# dabpi_v11.net
KiCad netlist of a schematic drawn in EAGLE
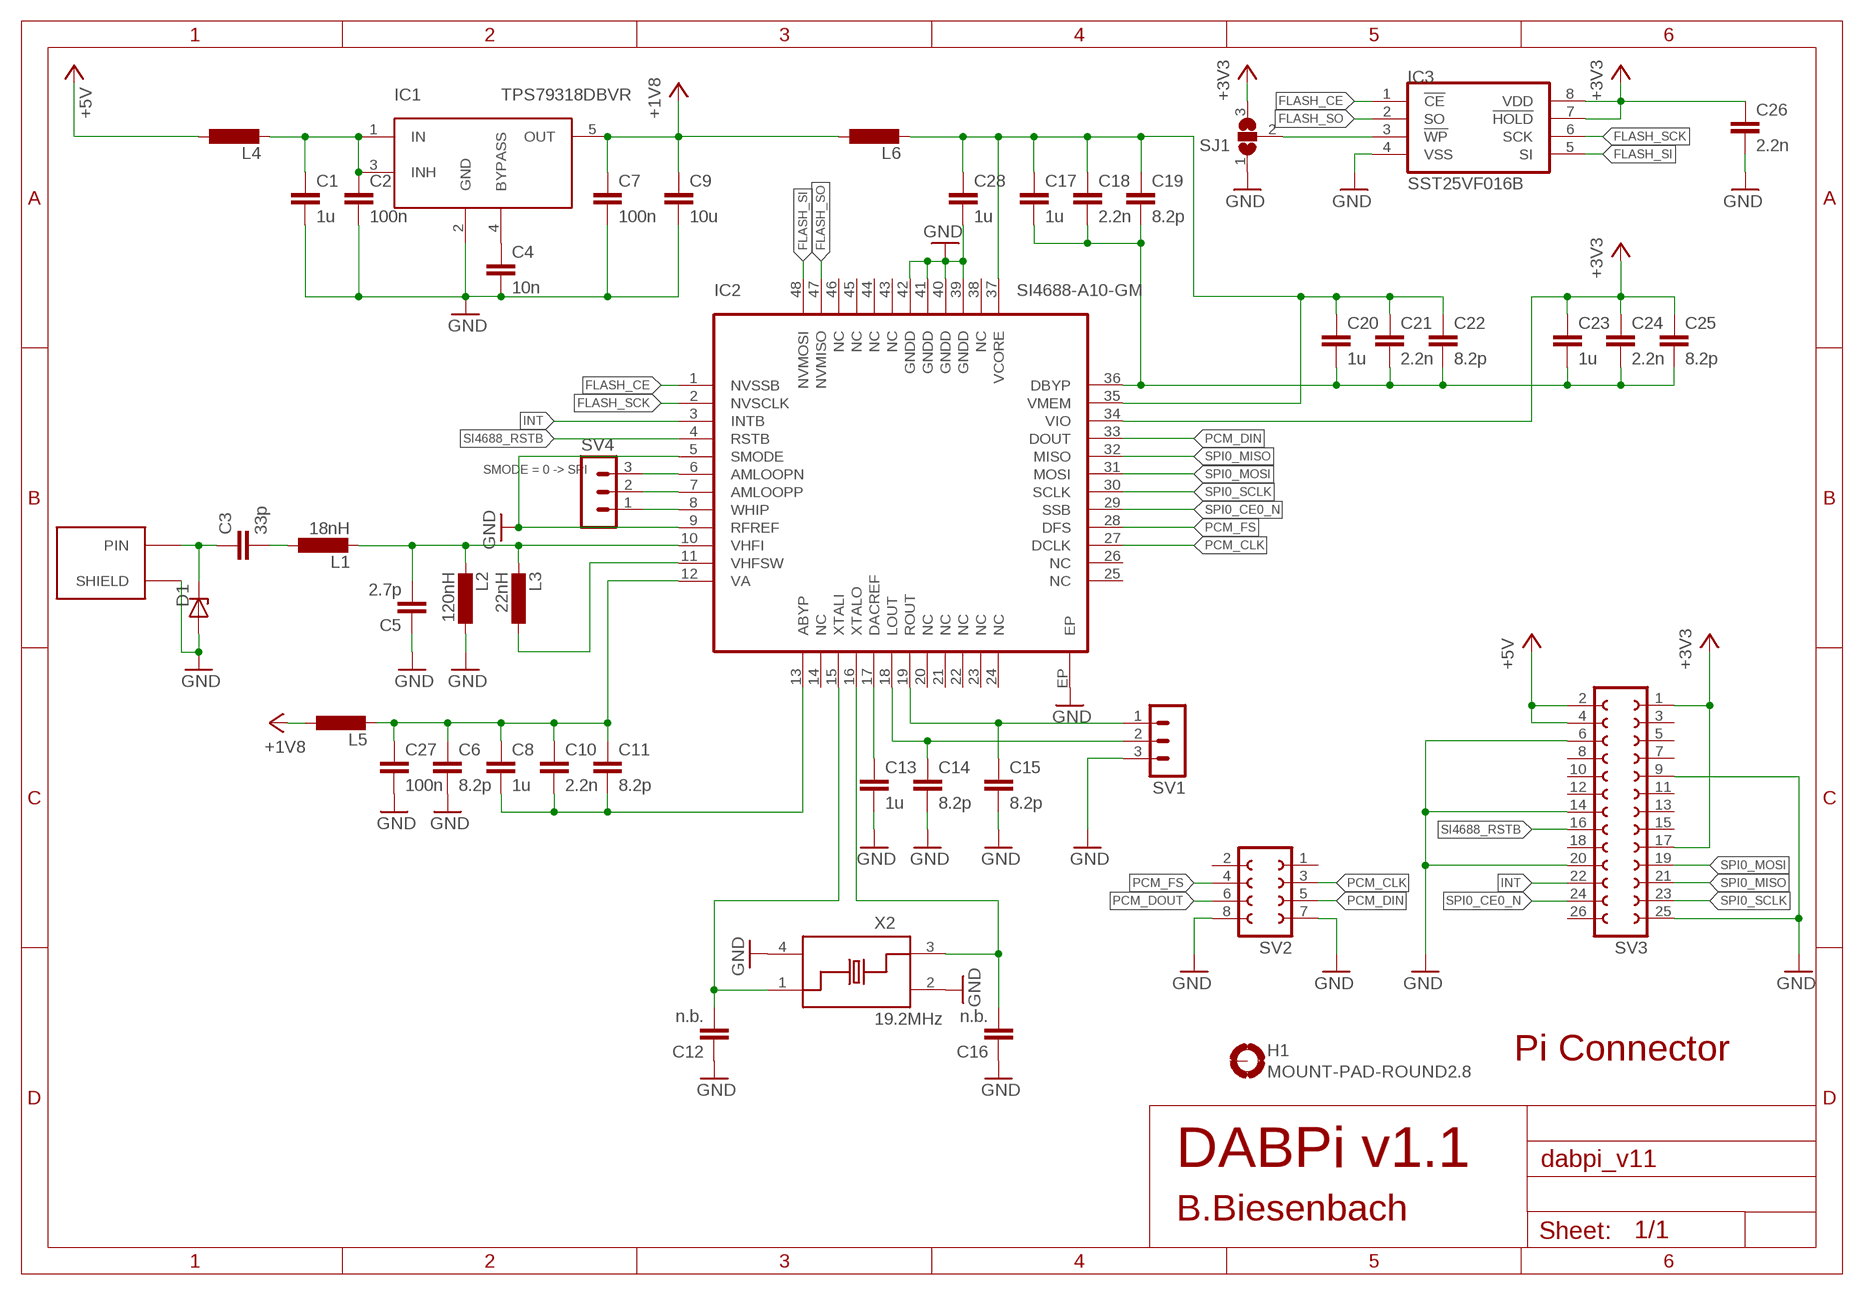
[diagram p0: schematic, sheet 1]

(export (version "E")
  (design (tool "Eeschema 10.0.6"))
  (components
    (comp (ref "C1")
      (value "1u")
      (footprint "eagle-import:SMD0603")
      (libsource (lib "eagle-import") (part "C0603"))
    )
    (comp (ref "C2")
      (value "100n")
      (footprint "eagle-import:SMD0603")
      (libsource (lib "eagle-import") (part "C0603"))
    )
    (comp (ref "C3")
      (value "33p")
      (footprint "eagle-import:SMD0402")
      (libsource (lib "eagle-import") (part "C0402"))
    )
    (comp (ref "C4")
      (value "10n")
      (footprint "eagle-import:SMD0603")
      (libsource (lib "eagle-import") (part "C0603"))
    )
    (comp (ref "C5")
      (value "2.7p")
      (footprint "eagle-import:SMD0402")
      (libsource (lib "eagle-import") (part "C0402"))
    )
    (comp (ref "C6")
      (value "8.2p")
      (footprint "eagle-import:SMD0603")
      (libsource (lib "eagle-import") (part "C0603"))
    )
    (comp (ref "C7")
      (value "100n")
      (footprint "eagle-import:SMD0603")
      (libsource (lib "eagle-import") (part "C0603"))
    )
    (comp (ref "C8")
      (value "1u")
      (footprint "eagle-import:SMD0603")
      (libsource (lib "eagle-import") (part "C0603"))
    )
    (comp (ref "C9")
      (value "10u")
      (footprint "eagle-import:SMD0603")
      (libsource (lib "eagle-import") (part "C0603"))
    )
    (comp (ref "C10")
      (value "2.2n")
      (footprint "eagle-import:SMD0603")
      (libsource (lib "eagle-import") (part "C0603"))
    )
    (comp (ref "C11")
      (value "8.2p")
      (footprint "eagle-import:SMD0603")
      (libsource (lib "eagle-import") (part "C0603"))
    )
    (comp (ref "C12")
      (value "n.b.")
      (footprint "eagle-import:SMD0402")
      (libsource (lib "eagle-import") (part "C0402"))
    )
    (comp (ref "C13")
      (value "1u")
      (footprint "eagle-import:SMD0603")
      (libsource (lib "eagle-import") (part "C0603"))
    )
    (comp (ref "C14")
      (value "8.2p")
      (footprint "eagle-import:SMD0603")
      (libsource (lib "eagle-import") (part "C0603"))
    )
    (comp (ref "C15")
      (value "8.2p")
      (footprint "eagle-import:SMD0603")
      (libsource (lib "eagle-import") (part "C0603"))
    )
    (comp (ref "C16")
      (value "n.b.")
      (footprint "eagle-import:SMD0402")
      (libsource (lib "eagle-import") (part "C0402"))
    )
    (comp (ref "C17")
      (value "1u")
      (footprint "eagle-import:SMD0603")
      (libsource (lib "eagle-import") (part "C0603"))
    )
    (comp (ref "C18")
      (value "2.2n")
      (footprint "eagle-import:SMD0603")
      (libsource (lib "eagle-import") (part "C0603"))
    )
    (comp (ref "C19")
      (value "8.2p")
      (footprint "eagle-import:SMD0603")
      (libsource (lib "eagle-import") (part "C0603"))
    )
    (comp (ref "C20")
      (value "1u")
      (footprint "eagle-import:SMD0603")
      (libsource (lib "eagle-import") (part "C0603"))
    )
    (comp (ref "C21")
      (value "2.2n")
      (footprint "eagle-import:SMD0603")
      (libsource (lib "eagle-import") (part "C0603"))
    )
    (comp (ref "C22")
      (value "8.2p")
      (footprint "eagle-import:SMD0603")
      (libsource (lib "eagle-import") (part "C0603"))
    )
    (comp (ref "C23")
      (value "1u")
      (footprint "eagle-import:SMD0603")
      (libsource (lib "eagle-import") (part "C0603"))
    )
    (comp (ref "C24")
      (value "2.2n")
      (footprint "eagle-import:SMD0603")
      (libsource (lib "eagle-import") (part "C0603"))
    )
    (comp (ref "C25")
      (value "8.2p")
      (footprint "eagle-import:SMD0603")
      (libsource (lib "eagle-import") (part "C0603"))
    )
    (comp (ref "C26")
      (value "2.2n")
      (footprint "eagle-import:SMD0603")
      (libsource (lib "eagle-import") (part "C0603"))
    )
    (comp (ref "C27")
      (value "100n")
      (footprint "eagle-import:SMD0603")
      (libsource (lib "eagle-import") (part "C0603"))
    )
    (comp (ref "C28")
      (value "1u")
      (footprint "eagle-import:SMD0603")
      (libsource (lib "eagle-import") (part "C0603"))
    )
    (comp (ref "D1")
      (value "ESD9L5.0")
      (footprint "eagle-import:SOD923")
      (libsource (lib "eagle-import") (part "ESD9L5.0"))
    )
    (comp (ref "H1")
      (value "MOUNT-PAD-ROUND2.8")
      (footprint "eagle-import:2,8-PAD")
      (libsource (lib "eagle-import") (part "MOUNT-PAD-ROUND2.8"))
    )
    (comp (ref "IC1")
      (value "TPS79318DBVR")
      (footprint "eagle-import:SOT23-5")
      (libsource (lib "eagle-import") (part "TPS79318DBVR"))
    )
    (comp (ref "IC2")
      (value "SI4688-A10-GM")
      (footprint "eagle-import:QFN48")
      (libsource (lib "eagle-import") (part "SI4688-A10-GM"))
    )
    (comp (ref "IC3")
      (value "SST25VF016B")
      (footprint "eagle-import:SO08")
      (libsource (lib "eagle-import") (part "SST25VF016B"))
    )
    (comp (ref "L1")
      (value "18nH")
      (footprint "eagle-import:SMD0402")
      (libsource (lib "eagle-import") (part "L0402"))
    )
    (comp (ref "L2")
      (value "120nH")
      (footprint "eagle-import:SMD0402")
      (libsource (lib "eagle-import") (part "L0402"))
    )
    (comp (ref "L3")
      (value "22nH")
      (footprint "eagle-import:SMD0402")
      (libsource (lib "eagle-import") (part "L0402"))
    )
    (comp (ref "L4")
      (value "L0603")
      (footprint "eagle-import:SMD0603")
      (libsource (lib "eagle-import") (part "L0603"))
    )
    (comp (ref "L5")
      (value "L0603")
      (footprint "eagle-import:SMD0603")
      (libsource (lib "eagle-import") (part "L0603"))
    )
    (comp (ref "L6")
      (value "L0603")
      (footprint "eagle-import:SMD0603")
      (libsource (lib "eagle-import") (part "L0603"))
    )
    (comp (ref "SJ1")
      (value "SJ2W")
      (footprint "eagle-import:SJ_2")
      (libsource (lib "eagle-import") (part "SJ2W"))
    )
    (comp (ref "SV1")
      (value "MA03-1")
      (footprint "eagle-import:MA03-1")
      (libsource (lib "eagle-import") (part "MA03-1"))
    )
    (comp (ref "SV2")
      (value "FE04-2")
      (footprint "eagle-import:FE04-2")
      (libsource (lib "eagle-import") (part "FE04-2"))
    )
    (comp (ref "SV3")
      (value "FE13-2")
      (footprint "eagle-import:FE13-2")
      (libsource (lib "eagle-import") (part "FE13-2"))
    )
    (comp (ref "SV4")
      (value "MA03-1")
      (footprint "eagle-import:MA03-1")
      (libsource (lib "eagle-import") (part "MA03-1"))
    )
    (comp (ref "X1")
      (value "SMA_LP_1.57MM")
      (footprint "eagle-import:SMA_LP_1.57MM")
      (libsource (lib "eagle-import") (part "SMA_LP_1.57MM"))
    )
    (comp (ref "X2")
      (value "19.2MHz")
      (footprint "eagle-import:XTAL_3.2X2.5")
      (libsource (lib "eagle-import") (part "XTAL_3.2X2.5"))
    )
  )
  (nets
    (net (code "1") (name "+1V8") (class "Default")
      (node (ref "C7") (pin "1") (pinfunction "1_1") (pintype "passive"))
      (node (ref "C9") (pin "1") (pinfunction "1_1") (pintype "passive"))
      (node (ref "IC1") (pin "5") (pinfunction "OUT_5") (pintype "power_in"))
      (node (ref "L5") (pin "1") (pinfunction "1_1") (pintype "passive"))
      (node (ref "L6") (pin "1") (pinfunction "1_1") (pintype "passive"))
    )
    (net (code "2") (name "+3V3") (class "Default")
      (node (ref "C23") (pin "1") (pinfunction "1_1") (pintype "passive"))
      (node (ref "C24") (pin "1") (pinfunction "1_1") (pintype "passive"))
      (node (ref "C25") (pin "1") (pinfunction "1_1") (pintype "passive"))
      (node (ref "C26") (pin "1") (pinfunction "1_1") (pintype "passive"))
      (node (ref "IC2") (pin "34") (pinfunction "VIO_34") (pintype "power_in"))
      (node (ref "IC3") (pin "7") (pinfunction "~{HOLD}_7") (pintype "input"))
      (node (ref "IC3") (pin "8") (pinfunction "VDD_8") (pintype "power_in"))
      (node (ref "SJ1") (pin "3") (pinfunction "3_3") (pintype "passive"))
      (node (ref "SV3") (pin "1") (pinfunction "1_1") (pintype "passive"))
      (node (ref "SV3") (pin "17") (pinfunction "17_17") (pintype "passive"))
    )
    (net (code "3") (name "+5V") (class "Default")
      (node (ref "L4") (pin "1") (pinfunction "1_1") (pintype "passive"))
      (node (ref "SV3") (pin "2") (pinfunction "2_2") (pintype "passive"))
      (node (ref "SV3") (pin "4") (pinfunction "4_4") (pintype "passive"))
    )
    (net (code "4") (name "FLASH_CE") (class "Default")
      (node (ref "IC2") (pin "1") (pinfunction "NVSSB_1") (pintype "output"))
      (node (ref "IC3") (pin "1") (pinfunction "~{CE}_1") (pintype "input"))
    )
    (net (code "5") (name "FLASH_SCK") (class "Default")
      (node (ref "IC2") (pin "2") (pinfunction "NVSCLK_2") (pintype "output"))
      (node (ref "IC3") (pin "6") (pinfunction "SCK_6") (pintype "input"))
    )
    (net (code "6") (name "FLASH_SI") (class "Default")
      (node (ref "IC2") (pin "48") (pinfunction "NVMOSI_48") (pintype "output"))
      (node (ref "IC3") (pin "5") (pinfunction "SI_5") (pintype "input"))
    )
    (net (code "7") (name "FLASH_SO") (class "Default")
      (node (ref "IC2") (pin "47") (pinfunction "NVMISO_47") (pintype "input"))
      (node (ref "IC3") (pin "2") (pinfunction "SO_2") (pintype "output"))
    )
    (net (code "8") (name "GND") (class "Default")
      (node (ref "C1") (pin "2") (pinfunction "2_2") (pintype "passive"))
      (node (ref "C12") (pin "1") (pinfunction "1_1") (pintype "passive"))
      (node (ref "C13") (pin "2") (pinfunction "2_2") (pintype "passive"))
      (node (ref "C14") (pin "2") (pinfunction "2_2") (pintype "passive"))
      (node (ref "C15") (pin "2") (pinfunction "2_2") (pintype "passive"))
      (node (ref "C16") (pin "1") (pinfunction "1_1") (pintype "passive"))
      (node (ref "C2") (pin "2") (pinfunction "2_2") (pintype "passive"))
      (node (ref "C26") (pin "2") (pinfunction "2_2") (pintype "passive"))
      (node (ref "C27") (pin "2") (pinfunction "2_2") (pintype "passive"))
      (node (ref "C28") (pin "2") (pinfunction "2_2") (pintype "passive"))
      (node (ref "C4") (pin "2") (pinfunction "2_2") (pintype "passive"))
      (node (ref "C5") (pin "1") (pinfunction "1_1") (pintype "passive"))
      (node (ref "C6") (pin "2") (pinfunction "2_2") (pintype "passive"))
      (node (ref "C7") (pin "2") (pinfunction "2_2") (pintype "passive"))
      (node (ref "C9") (pin "2") (pinfunction "2_2") (pintype "passive"))
      (node (ref "D1") (pin "A") (pinfunction "A_A") (pintype "passive"))
      (node (ref "IC1") (pin "2") (pinfunction "GND_2") (pintype "power_in"))
      (node (ref "IC2") (pin "39") (pinfunction "GNDD_39") (pintype "power_in"))
      (node (ref "IC2") (pin "40") (pinfunction "GNDD_40") (pintype "power_in"))
      (node (ref "IC2") (pin "41") (pinfunction "GNDD_41") (pintype "power_in"))
      (node (ref "IC2") (pin "42") (pinfunction "GNDD_42") (pintype "power_in"))
      (node (ref "IC2") (pin "5") (pinfunction "SMODE_5") (pintype "input"))
      (node (ref "IC2") (pin "9") (pinfunction "RFREF_9") (pintype "power_in"))
      (node (ref "IC2") (pin "EP") (pinfunction "EP_EP") (pintype "bidirectional"))
      (node (ref "IC3") (pin "4") (pinfunction "VSS_4") (pintype "power_in"))
      (node (ref "L2") (pin "1") (pinfunction "1_1") (pintype "passive"))
      (node (ref "SJ1") (pin "1") (pinfunction "1_1") (pintype "passive"))
      (node (ref "SV1") (pin "3") (pinfunction "3_3") (pintype "passive"))
      (node (ref "SV2") (pin "7") (pinfunction "7_7") (pintype "passive"))
      (node (ref "SV2") (pin "8") (pinfunction "8_8") (pintype "passive"))
      (node (ref "SV3") (pin "14") (pinfunction "14_14") (pintype "passive"))
      (node (ref "SV3") (pin "20") (pinfunction "20_20") (pintype "passive"))
      (node (ref "SV3") (pin "25") (pinfunction "25_25") (pintype "passive"))
      (node (ref "SV3") (pin "6") (pinfunction "6_6") (pintype "passive"))
      (node (ref "SV3") (pin "9") (pinfunction "9_9") (pintype "passive"))
      (node (ref "X1") (pin "GND") (pinfunction "SHIELD_GND") (pintype "power_in"))
      (node (ref "X1") (pin "GND@1") (pinfunction "SHIELD_GND@1") (pintype "power_in"))
      (node (ref "X1") (pin "GND@2") (pinfunction "SHIELD_GND@2") (pintype "power_in"))
      (node (ref "X1") (pin "GND@3") (pinfunction "SHIELD_GND@3") (pintype "power_in"))
      (node (ref "X2") (pin "2") (pinfunction "GND_2") (pintype "power_in"))
      (node (ref "X2") (pin "4") (pinfunction "GND_4") (pintype "power_in"))
    )
    (net (code "9") (name "INT") (class "Default")
      (node (ref "IC2") (pin "3") (pinfunction "INTB_3") (pintype "output"))
      (node (ref "SV3") (pin "22") (pinfunction "22_22") (pintype "passive"))
    )
    (net (code "10") (name "Net-(C3-Pad2)") (class "Default")
      (node (ref "C3") (pin "2") (pinfunction "2_2") (pintype "passive"))
      (node (ref "L1") (pin "1") (pinfunction "1_1") (pintype "passive"))
    )
    (net (code "11") (name "Net-(D1-C)") (class "Default")
      (node (ref "C3") (pin "1") (pinfunction "1_1") (pintype "passive"))
      (node (ref "D1") (pin "K") (pinfunction "C_K") (pintype "passive"))
      (node (ref "X1") (pin "PIN") (pinfunction "PIN_PIN") (pintype "passive"))
    )
    (net (code "12") (name "Net-(IC1-BYPASS)") (class "Default")
      (node (ref "C4") (pin "1") (pinfunction "1_1") (pintype "passive"))
      (node (ref "IC1") (pin "4") (pinfunction "BYPASS_4") (pintype "power_in"))
    )
    (net (code "13") (name "Net-(IC1-IN)") (class "Default")
      (node (ref "C1") (pin "1") (pinfunction "1_1") (pintype "passive"))
      (node (ref "C2") (pin "1") (pinfunction "1_1") (pintype "passive"))
      (node (ref "IC1") (pin "1") (pinfunction "IN_1") (pintype "power_in"))
      (node (ref "IC1") (pin "3") (pinfunction "INH_3") (pintype "input"))
      (node (ref "L4") (pin "2") (pinfunction "2_2") (pintype "passive"))
    )
    (net (code "14") (name "Net-(IC2-ABYP)") (class "Default")
      (node (ref "C10") (pin "2") (pinfunction "2_2") (pintype "passive"))
      (node (ref "C11") (pin "2") (pinfunction "2_2") (pintype "passive"))
      (node (ref "C8") (pin "2") (pinfunction "2_2") (pintype "passive"))
      (node (ref "IC2") (pin "13") (pinfunction "ABYP_13") (pintype "power_in"))
    )
    (net (code "15") (name "Net-(IC2-AMLOOPN)") (class "Default")
      (node (ref "IC2") (pin "6") (pinfunction "AMLOOPN_6") (pintype "power_in"))
      (node (ref "SV4") (pin "3") (pinfunction "3_3") (pintype "passive"))
    )
    (net (code "16") (name "Net-(IC2-AMLOOPP)") (class "Default")
      (node (ref "IC2") (pin "7") (pinfunction "AMLOOPP_7") (pintype "power_in"))
      (node (ref "SV4") (pin "2") (pinfunction "2_2") (pintype "passive"))
    )
    (net (code "17") (name "Net-(IC2-DACREF)") (class "Default")
      (node (ref "C13") (pin "1") (pinfunction "1_1") (pintype "passive"))
      (node (ref "IC2") (pin "17") (pinfunction "DACREF_17") (pintype "power_in"))
    )
    (net (code "18") (name "Net-(IC2-DBYP)") (class "Default")
      (node (ref "C17") (pin "2") (pinfunction "2_2") (pintype "passive"))
      (node (ref "C18") (pin "2") (pinfunction "2_2") (pintype "passive"))
      (node (ref "C19") (pin "2") (pinfunction "2_2") (pintype "passive"))
      (node (ref "C20") (pin "2") (pinfunction "2_2") (pintype "passive"))
      (node (ref "C21") (pin "2") (pinfunction "2_2") (pintype "passive"))
      (node (ref "C22") (pin "2") (pinfunction "2_2") (pintype "passive"))
      (node (ref "C23") (pin "2") (pinfunction "2_2") (pintype "passive"))
      (node (ref "C24") (pin "2") (pinfunction "2_2") (pintype "passive"))
      (node (ref "C25") (pin "2") (pinfunction "2_2") (pintype "passive"))
      (node (ref "IC2") (pin "36") (pinfunction "DBYP_36") (pintype "power_in"))
    )
    (net (code "19") (name "Net-(IC2-LOUT)") (class "Default")
      (node (ref "C14") (pin "1") (pinfunction "1_1") (pintype "passive"))
      (node (ref "IC2") (pin "18") (pinfunction "LOUT_18") (pintype "output"))
      (node (ref "SV1") (pin "2") (pinfunction "2_2") (pintype "passive"))
    )
    (net (code "20") (name "Net-(IC2-ROUT)") (class "Default")
      (node (ref "C15") (pin "1") (pinfunction "1_1") (pintype "passive"))
      (node (ref "IC2") (pin "19") (pinfunction "ROUT_19") (pintype "output"))
      (node (ref "SV1") (pin "1") (pinfunction "1_1") (pintype "passive"))
    )
    (net (code "21") (name "Net-(IC2-VA)") (class "Default")
      (node (ref "C10") (pin "1") (pinfunction "1_1") (pintype "passive"))
      (node (ref "C11") (pin "1") (pinfunction "1_1") (pintype "passive"))
      (node (ref "C27") (pin "1") (pinfunction "1_1") (pintype "passive"))
      (node (ref "C6") (pin "1") (pinfunction "1_1") (pintype "passive"))
      (node (ref "C8") (pin "1") (pinfunction "1_1") (pintype "passive"))
      (node (ref "IC2") (pin "12") (pinfunction "VA_12") (pintype "power_in"))
      (node (ref "L5") (pin "2") (pinfunction "2_2") (pintype "passive"))
    )
    (net (code "22") (name "Net-(IC2-VCORE)") (class "Default")
      (node (ref "C17") (pin "1") (pinfunction "1_1") (pintype "passive"))
      (node (ref "C18") (pin "1") (pinfunction "1_1") (pintype "passive"))
      (node (ref "C19") (pin "1") (pinfunction "1_1") (pintype "passive"))
      (node (ref "C20") (pin "1") (pinfunction "1_1") (pintype "passive"))
      (node (ref "C21") (pin "1") (pinfunction "1_1") (pintype "passive"))
      (node (ref "C22") (pin "1") (pinfunction "1_1") (pintype "passive"))
      (node (ref "C28") (pin "1") (pinfunction "1_1") (pintype "passive"))
      (node (ref "IC2") (pin "35") (pinfunction "VMEM_35") (pintype "power_in"))
      (node (ref "IC2") (pin "37") (pinfunction "VCORE_37") (pintype "power_in"))
      (node (ref "L6") (pin "2") (pinfunction "2_2") (pintype "passive"))
    )
    (net (code "23") (name "Net-(IC2-VHFI)") (class "Default")
      (node (ref "C5") (pin "2") (pinfunction "2_2") (pintype "passive"))
      (node (ref "IC2") (pin "10") (pinfunction "VHFI_10") (pintype "input"))
      (node (ref "L1") (pin "2") (pinfunction "2_2") (pintype "passive"))
      (node (ref "L2") (pin "2") (pinfunction "2_2") (pintype "passive"))
      (node (ref "L3") (pin "2") (pinfunction "2_2") (pintype "passive"))
    )
    (net (code "24") (name "Net-(IC2-VHFSW)") (class "Default")
      (node (ref "IC2") (pin "11") (pinfunction "VHFSW_11") (pintype "output"))
      (node (ref "L3") (pin "1") (pinfunction "1_1") (pintype "passive"))
    )
    (net (code "25") (name "Net-(IC2-WHIP)") (class "Default")
      (node (ref "IC2") (pin "8") (pinfunction "WHIP_8") (pintype "power_in"))
      (node (ref "SV4") (pin "1") (pinfunction "1_1") (pintype "passive"))
    )
    (net (code "26") (name "Net-(IC2-XTALI)") (class "Default")
      (node (ref "C12") (pin "2") (pinfunction "2_2") (pintype "passive"))
      (node (ref "IC2") (pin "15") (pinfunction "XTALI_15") (pintype "input"))
      (node (ref "X2") (pin "1") (pinfunction "1_1") (pintype "passive"))
    )
    (net (code "27") (name "Net-(IC2-XTALO)") (class "Default")
      (node (ref "C16") (pin "2") (pinfunction "2_2") (pintype "passive"))
      (node (ref "IC2") (pin "16") (pinfunction "XTALO_16") (pintype "output"))
      (node (ref "X2") (pin "3") (pinfunction "3_3") (pintype "passive"))
    )
    (net (code "28") (name "Net-(IC3-~{WP})") (class "Default")
      (node (ref "IC3") (pin "3") (pinfunction "~{WP}_3") (pintype "input"))
      (node (ref "SJ1") (pin "2") (pinfunction "2_2") (pintype "passive"))
    )
    (net (code "29") (name "PCM_CLK") (class "Default")
      (node (ref "IC2") (pin "27") (pinfunction "DCLK_27") (pintype "bidirectional"))
      (node (ref "SV2") (pin "3") (pinfunction "3_3") (pintype "passive"))
    )
    (net (code "30") (name "PCM_DIN") (class "Default")
      (node (ref "IC2") (pin "33") (pinfunction "DOUT_33") (pintype "output"))
      (node (ref "SV2") (pin "5") (pinfunction "5_5") (pintype "passive"))
    )
    (net (code "31") (name "PCM_DOUT") (class "Default")
      (node (ref "SV2") (pin "6") (pinfunction "6_6") (pintype "passive"))
    )
    (net (code "32") (name "PCM_FS") (class "Default")
      (node (ref "IC2") (pin "28") (pinfunction "DFS_28") (pintype "bidirectional"))
      (node (ref "SV2") (pin "4") (pinfunction "4_4") (pintype "passive"))
    )
    (net (code "33") (name "SI4688_RSTB") (class "Default")
      (node (ref "IC2") (pin "4") (pinfunction "RSTB_4") (pintype "input"))
      (node (ref "SV3") (pin "16") (pinfunction "16_16") (pintype "passive"))
    )
    (net (code "34") (name "SPI0_CE0_N") (class "Default")
      (node (ref "IC2") (pin "29") (pinfunction "SSB_29") (pintype "input"))
      (node (ref "SV3") (pin "24") (pinfunction "24_24") (pintype "passive"))
    )
    (net (code "35") (name "SPI0_MISO") (class "Default")
      (node (ref "IC2") (pin "32") (pinfunction "MISO_32") (pintype "bidirectional"))
      (node (ref "SV3") (pin "21") (pinfunction "21_21") (pintype "passive"))
    )
    (net (code "36") (name "SPI0_MOSI") (class "Default")
      (node (ref "IC2") (pin "31") (pinfunction "MOSI_31") (pintype "bidirectional"))
      (node (ref "SV3") (pin "19") (pinfunction "19_19") (pintype "passive"))
    )
    (net (code "37") (name "SPI0_SCLK") (class "Default")
      (node (ref "IC2") (pin "30") (pinfunction "SCLK_30") (pintype "input"))
      (node (ref "SV3") (pin "23") (pinfunction "23_23") (pintype "passive"))
    )
    (net (code "38") (name "unconnected-(H1-MOUNT-PadB2,8)") (class "Default")
      (node (ref "H1") (pin "B2,8") (pinfunction "MOUNT_B2,8") (pintype "passive"))
    )
    (net (code "39") (name "unconnected-(IC2-NC-Pad14)") (class "Default")
      (node (ref "IC2") (pin "14") (pinfunction "NC_14") (pintype "no_connect"))
    )
    (net (code "40") (name "unconnected-(IC2-NC-Pad20)") (class "Default")
      (node (ref "IC2") (pin "20") (pinfunction "NC_20") (pintype "no_connect"))
    )
    (net (code "41") (name "unconnected-(IC2-NC-Pad21)") (class "Default")
      (node (ref "IC2") (pin "21") (pinfunction "NC_21") (pintype "no_connect"))
    )
    (net (code "42") (name "unconnected-(IC2-NC-Pad22)") (class "Default")
      (node (ref "IC2") (pin "22") (pinfunction "NC_22") (pintype "no_connect"))
    )
    (net (code "43") (name "unconnected-(IC2-NC-Pad23)") (class "Default")
      (node (ref "IC2") (pin "23") (pinfunction "NC_23") (pintype "no_connect"))
    )
    (net (code "44") (name "unconnected-(IC2-NC-Pad24)") (class "Default")
      (node (ref "IC2") (pin "24") (pinfunction "NC_24") (pintype "no_connect"))
    )
    (net (code "45") (name "unconnected-(IC2-NC-Pad25)") (class "Default")
      (node (ref "IC2") (pin "25") (pinfunction "NC_25") (pintype "no_connect"))
    )
    (net (code "46") (name "unconnected-(IC2-NC-Pad26)") (class "Default")
      (node (ref "IC2") (pin "26") (pinfunction "NC_26") (pintype "no_connect"))
    )
    (net (code "47") (name "unconnected-(IC2-NC-Pad38)") (class "Default")
      (node (ref "IC2") (pin "38") (pinfunction "NC_38") (pintype "no_connect"))
    )
    (net (code "48") (name "unconnected-(IC2-NC-Pad43)") (class "Default")
      (node (ref "IC2") (pin "43") (pinfunction "NC_43") (pintype "no_connect"))
    )
    (net (code "49") (name "unconnected-(IC2-NC-Pad44)") (class "Default")
      (node (ref "IC2") (pin "44") (pinfunction "NC_44") (pintype "no_connect"))
    )
    (net (code "50") (name "unconnected-(IC2-NC-Pad45)") (class "Default")
      (node (ref "IC2") (pin "45") (pinfunction "NC_45") (pintype "no_connect"))
    )
    (net (code "51") (name "unconnected-(IC2-NC-Pad46)") (class "Default")
      (node (ref "IC2") (pin "46") (pinfunction "NC_46") (pintype "no_connect"))
    )
    (net (code "52") (name "unconnected-(SV2-Pad1)") (class "Default")
      (node (ref "SV2") (pin "1") (pinfunction "1_1") (pintype "passive"))
    )
    (net (code "53") (name "unconnected-(SV2-Pad2)") (class "Default")
      (node (ref "SV2") (pin "2") (pinfunction "2_2") (pintype "passive"))
    )
    (net (code "54") (name "unconnected-(SV3-Pad3)") (class "Default")
      (node (ref "SV3") (pin "3") (pinfunction "3_3") (pintype "passive"))
    )
    (net (code "55") (name "unconnected-(SV3-Pad5)") (class "Default")
      (node (ref "SV3") (pin "5") (pinfunction "5_5") (pintype "passive"))
    )
    (net (code "56") (name "unconnected-(SV3-Pad7)") (class "Default")
      (node (ref "SV3") (pin "7") (pinfunction "7_7") (pintype "passive"))
    )
    (net (code "57") (name "unconnected-(SV3-Pad8)") (class "Default")
      (node (ref "SV3") (pin "8") (pinfunction "8_8") (pintype "passive"))
    )
    (net (code "58") (name "unconnected-(SV3-Pad10)") (class "Default")
      (node (ref "SV3") (pin "10") (pinfunction "10_10") (pintype "passive"))
    )
    (net (code "59") (name "unconnected-(SV3-Pad11)") (class "Default")
      (node (ref "SV3") (pin "11") (pinfunction "11_11") (pintype "passive"))
    )
    (net (code "60") (name "unconnected-(SV3-Pad12)") (class "Default")
      (node (ref "SV3") (pin "12") (pinfunction "12_12") (pintype "passive"))
    )
    (net (code "61") (name "unconnected-(SV3-Pad13)") (class "Default")
      (node (ref "SV3") (pin "13") (pinfunction "13_13") (pintype "passive"))
    )
    (net (code "62") (name "unconnected-(SV3-Pad15)") (class "Default")
      (node (ref "SV3") (pin "15") (pinfunction "15_15") (pintype "passive"))
    )
    (net (code "63") (name "unconnected-(SV3-Pad18)") (class "Default")
      (node (ref "SV3") (pin "18") (pinfunction "18_18") (pintype "passive"))
    )
    (net (code "64") (name "unconnected-(SV3-Pad26)") (class "Default")
      (node (ref "SV3") (pin "26") (pinfunction "26_26") (pintype "passive"))
    )
  )
)
